# CLOCK_IO.net
KiCad netlist of a schematic drawn in Altium Designer
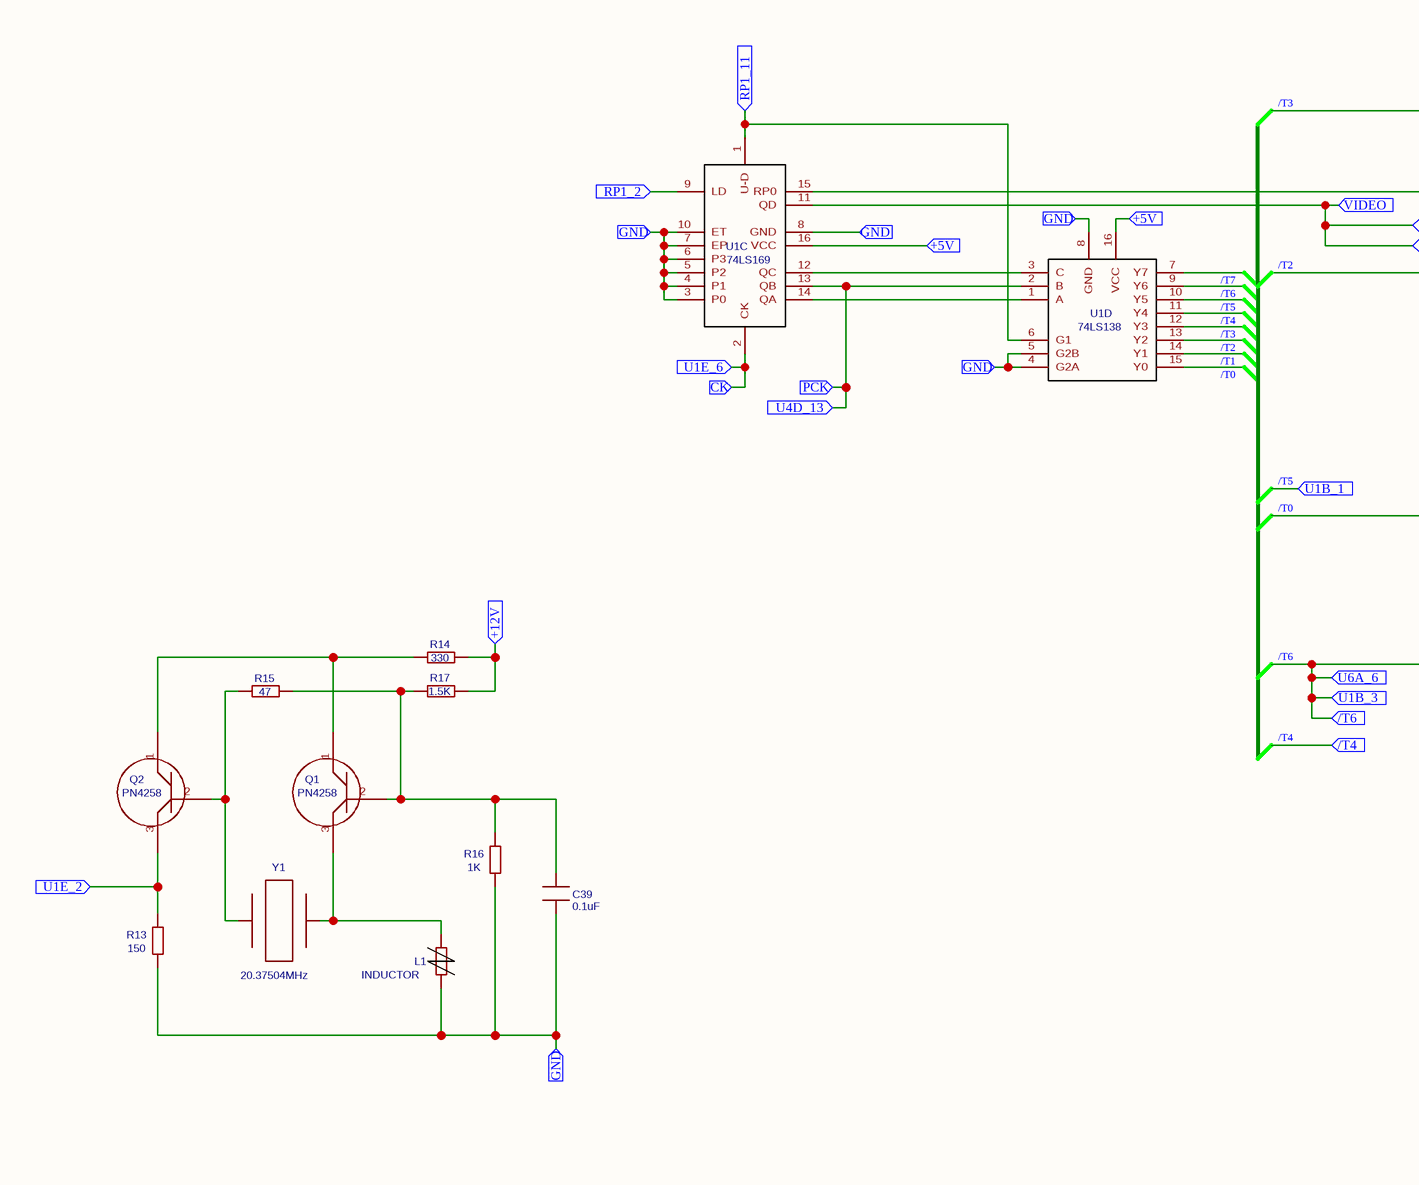
[diagram p0: CLOCK+IO.schdoc, left]
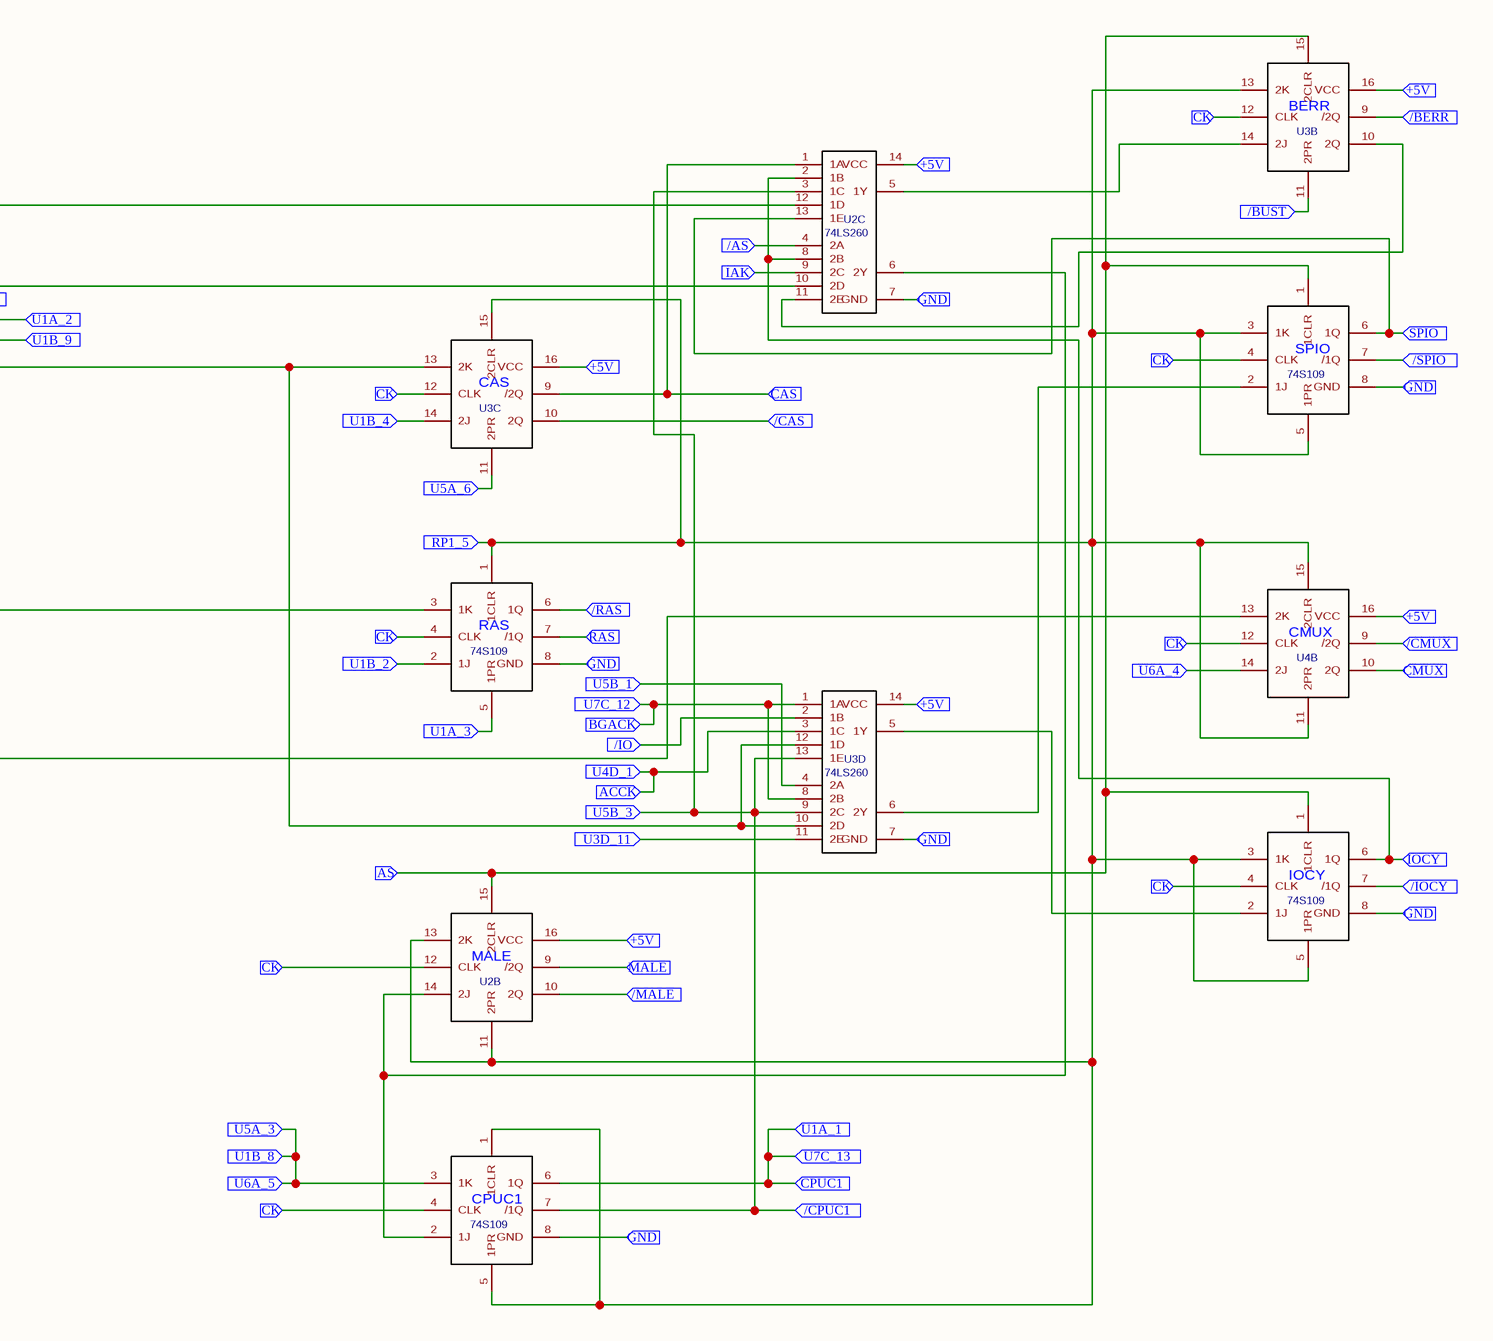
[diagram p1: CLOCK+IO.schdoc, right]

(export (version "E")
  (design (tool "Eeschema 10.0.6"))
  (components
    (comp (ref "C39")
      (value "0.1uF")
      (fields (field (name "CONTRIBUTOR") "William Tooker"))
      (libsource (lib "altium-import") (part "root_3_0.1uF_"))
    )
    (comp (ref "L1")
      (value "INDUCTOR")
      (fields (field (name "CONTRIBUTOR") "William Tooker"))
      (libsource (lib "altium-import") (part "root_3_INDUCTOR_"))
    )
    (comp (ref "Q1")
      (value "PN4258")
      (fields (field (name "CONTRIBUTOR") "William Tooker"))
      (libsource (lib "altium-import") (part "root_0_PN4258_"))
    )
    (comp (ref "Q2")
      (value "PN4258")
      (fields (field (name "CONTRIBUTOR") "William Tooker"))
      (libsource (lib "altium-import") (part "root_0_PN4258_"))
    )
    (comp (ref "R13")
      (value "150")
      (fields (field (name "CONTRIBUTOR") "William Tooker"))
      (libsource (lib "altium-import") (part "root_1_150_"))
    )
    (comp (ref "R14")
      (value "330")
      (fields (field (name "CONTRIBUTOR") "William Tooker"))
      (libsource (lib "altium-import") (part "root_0_330_"))
    )
    (comp (ref "R15")
      (value "47")
      (fields (field (name "CONTRIBUTOR") "William Tooker"))
      (libsource (lib "altium-import") (part "root_0_47_"))
    )
    (comp (ref "R16")
      (value "1K")
      (fields (field (name "CONTRIBUTOR") "William Tooker"))
      (libsource (lib "altium-import") (part "root_1_1K_"))
    )
    (comp (ref "R17")
      (value "1.5K")
      (fields (field (name "CONTRIBUTOR") "William Tooker"))
      (libsource (lib "altium-import") (part "root_0_1.5K_"))
    )
    (comp (ref "U1C")
      (value "74LS169")
      (fields (field (name "CONTRIBUTOR") "William Tooker"))
      (libsource (lib "altium-import") (part "root_0_74LS169_"))
    )
    (comp (ref "U1D")
      (value "74LS138")
      (fields (field (name "CONTRIBUTOR") "William Tooker"))
      (libsource (lib "altium-import") (part "root_0_74LS138_"))
    )
    (comp (ref "U2B")
      (value "74S109")
      (fields (field (name "CONTRIBUTOR") "William Tooker"))
      (libsource (lib "altium-import") (part "root_0_74S109_"))
    )
    (comp (ref "U2C")
      (value "74LS260")
      (fields (field (name "CONTRIBUTOR") "William Tooker"))
      (libsource (lib "altium-import") (part "root_0_74LS260_"))
    )
    (comp (ref "U3B")
      (value "74S109")
      (fields (field (name "CONTRIBUTOR") "William Tooker"))
      (libsource (lib "altium-import") (part "root_0_74S109_"))
    )
    (comp (ref "U3C")
      (value "74S109")
      (fields (field (name "CONTRIBUTOR") "William Tooker"))
      (libsource (lib "altium-import") (part "root_0_74S109_"))
    )
    (comp (ref "U3D")
      (value "74LS260")
      (fields (field (name "CONTRIBUTOR") "William Tooker"))
      (libsource (lib "altium-import") (part "root_0_74LS260_"))
    )
    (comp (ref "U4B")
      (value "74S109")
      (fields (field (name "CONTRIBUTOR") "William Tooker"))
      (libsource (lib "altium-import") (part "root_0_74S109_"))
    )
    (comp (ref "Y1")
      (value "20.37504MHz")
      (fields (field (name "CONTRIBUTOR") "William Tooker"))
      (libsource (lib "altium-import") (part "root_0_20.37504MHz_"))
    )
  )
  (nets
    (net (code "1") (name "/+5V") (class "Default")
      (node (ref "U1C") (pin "16") (pinfunction "VCC_16") (pintype "passive"))
      (node (ref "U1D") (pin "16") (pinfunction "VCC_16") (pintype "passive"))
      (node (ref "U2B") (pin "16") (pinfunction "VCC_16") (pintype "passive"))
      (node (ref "U2C") (pin "14") (pinfunction "VCC_14") (pintype "passive"))
      (node (ref "U3B") (pin "16") (pinfunction "VCC_16") (pintype "passive"))
      (node (ref "U3C") (pin "16") (pinfunction "VCC_16") (pintype "passive"))
      (node (ref "U3D") (pin "14") (pinfunction "VCC_14") (pintype "passive"))
      (node (ref "U4B") (pin "16") (pinfunction "VCC_16") (pintype "passive"))
    )
    (net (code "2") (name "/+12V") (class "Default")
      (node (ref "R14") (pin "2") (pinfunction "2_2") (pintype "passive"))
      (node (ref "R17") (pin "2") (pinfunction "2_2") (pintype "passive"))
    )
    (net (code "3") (name "/ACCK") (class "Default")
      (node (ref "U3D") (pin "3") (pinfunction "1C_3") (pintype "passive"))
    )
    (net (code "4") (name "/AS") (class "Default")
      (node (ref "U2B") (pin "15") (pinfunction "2CLR_15") (pintype "passive"))
      (node (ref "U3B") (pin "1") (pinfunction "1CLR_1") (pintype "passive"))
      (node (ref "U3B") (pin "15") (pinfunction "2CLR_15") (pintype "passive"))
      (node (ref "U4B") (pin "1") (pinfunction "1CLR_1") (pintype "passive"))
    )
    (net (code "5") (name "/BGACK") (class "Default")
      (node (ref "U3D") (pin "1") (pinfunction "1A_1") (pintype "passive"))
      (node (ref "U3D") (pin "8") (pinfunction "2B_8") (pintype "passive"))
    )
    (net (code "6") (name "/CAS") (class "Default")
      (node (ref "U2C") (pin "1") (pinfunction "1A_1") (pintype "passive"))
      (node (ref "U3C") (pin "9") (pinfunction "/2Q_9") (pintype "passive"))
    )
    (net (code "7") (name "/CK") (class "Default")
      (node (ref "U1C") (pin "2") (pinfunction "CK_2") (pintype "passive"))
      (node (ref "U2B") (pin "12") (pinfunction "CLK_12") (pintype "passive"))
      (node (ref "U2B") (pin "4") (pinfunction "CLK_4") (pintype "passive"))
      (node (ref "U3B") (pin "12") (pinfunction "CLK_12") (pintype "passive"))
      (node (ref "U3B") (pin "4") (pinfunction "CLK_4") (pintype "passive"))
      (node (ref "U3C") (pin "12") (pinfunction "CLK_12") (pintype "passive"))
      (node (ref "U3C") (pin "4") (pinfunction "CLK_4") (pintype "passive"))
      (node (ref "U4B") (pin "12") (pinfunction "CLK_12") (pintype "passive"))
      (node (ref "U4B") (pin "4") (pinfunction "CLK_4") (pintype "passive"))
    )
    (net (code "8") (name "/CMUX") (class "Default")
      (node (ref "U4B") (pin "10") (pinfunction "2Q_10") (pintype "passive"))
    )
    (net (code "9") (name "/CPUC1") (class "Default")
      (node (ref "U2B") (pin "6") (pinfunction "1Q_6") (pintype "passive"))
    )
    (net (code "10") (name "/GND") (class "Default")
      (node (ref "C39") (pin "2") (pinfunction "2_2") (pintype "passive"))
      (node (ref "L1") (pin "2") (pinfunction "2_2") (pintype "passive"))
      (node (ref "R13") (pin "1") (pinfunction "1_1") (pintype "passive"))
      (node (ref "R16") (pin "1") (pinfunction "1_1") (pintype "passive"))
      (node (ref "U1C") (pin "10") (pinfunction "ET_10") (pintype "passive"))
      (node (ref "U1C") (pin "3") (pinfunction "P0_3") (pintype "passive"))
      (node (ref "U1C") (pin "4") (pinfunction "P1_4") (pintype "passive"))
      (node (ref "U1C") (pin "5") (pinfunction "P2_5") (pintype "passive"))
      (node (ref "U1C") (pin "6") (pinfunction "P3_6") (pintype "passive"))
      (node (ref "U1C") (pin "7") (pinfunction "EP_7") (pintype "passive"))
      (node (ref "U1C") (pin "8") (pinfunction "GND_8") (pintype "passive"))
      (node (ref "U1D") (pin "4") (pinfunction "G2A_4") (pintype "passive"))
      (node (ref "U1D") (pin "5") (pinfunction "G2B_5") (pintype "passive"))
      (node (ref "U1D") (pin "8") (pinfunction "GND_8") (pintype "passive"))
      (node (ref "U2B") (pin "8") (pinfunction "GND_8") (pintype "passive"))
      (node (ref "U2C") (pin "7") (pinfunction "GND_7") (pintype "passive"))
      (node (ref "U3B") (pin "8") (pinfunction "GND_8") (pintype "passive"))
      (node (ref "U3C") (pin "8") (pinfunction "GND_8") (pintype "passive"))
      (node (ref "U3D") (pin "7") (pinfunction "GND_7") (pintype "passive"))
      (node (ref "U4B") (pin "8") (pinfunction "GND_8") (pintype "passive"))
    )
    (net (code "11") (name "/IAK") (class "Default")
      (node (ref "U2C") (pin "9") (pinfunction "2C_9") (pintype "passive"))
    )
    (net (code "12") (name "/IOCY") (class "Default")
      (node (ref "U2C") (pin "2") (pinfunction "1B_2") (pintype "passive"))
      (node (ref "U2C") (pin "8") (pinfunction "2B_8") (pintype "passive"))
      (node (ref "U4B") (pin "6") (pinfunction "1Q_6") (pintype "passive"))
    )
    (net (code "13") (name "/MALE") (class "Default")
      (node (ref "U2B") (pin "9") (pinfunction "/2Q_9") (pintype "passive"))
    )
    (net (code "14") (name "/PCK") (class "Default")
      (node (ref "U1C") (pin "13") (pinfunction "QB_13") (pintype "passive"))
      (node (ref "U1D") (pin "2") (pinfunction "B_2") (pintype "passive"))
    )
    (net (code "15") (name "/RAS") (class "Default")
      (node (ref "U3C") (pin "7") (pinfunction "/1Q_7") (pintype "passive"))
    )
    (net (code "16") (name "/RP1_2") (class "Default")
      (node (ref "U1C") (pin "9") (pinfunction "LD_9") (pintype "passive"))
    )
    (net (code "17") (name "/RP1_5") (class "Default")
      (node (ref "U2B") (pin "1") (pinfunction "1CLR_1") (pintype "passive"))
      (node (ref "U2B") (pin "11") (pinfunction "2PR_11") (pintype "passive"))
      (node (ref "U2B") (pin "13") (pinfunction "2K_13") (pintype "passive"))
      (node (ref "U2B") (pin "5") (pinfunction "1PR_5") (pintype "passive"))
      (node (ref "U3B") (pin "13") (pinfunction "2K_13") (pintype "passive"))
      (node (ref "U3B") (pin "3") (pinfunction "1K_3") (pintype "passive"))
      (node (ref "U3B") (pin "5") (pinfunction "1PR_5") (pintype "passive"))
      (node (ref "U3C") (pin "1") (pinfunction "1CLR_1") (pintype "passive"))
      (node (ref "U3C") (pin "15") (pinfunction "2CLR_15") (pintype "passive"))
      (node (ref "U4B") (pin "11") (pinfunction "2PR_11") (pintype "passive"))
      (node (ref "U4B") (pin "15") (pinfunction "2CLR_15") (pintype "passive"))
      (node (ref "U4B") (pin "3") (pinfunction "1K_3") (pintype "passive"))
      (node (ref "U4B") (pin "5") (pinfunction "1PR_5") (pintype "passive"))
    )
    (net (code "18") (name "/RP1_11") (class "Default")
      (node (ref "U1C") (pin "1") (pinfunction "U-D_1") (pintype "passive"))
      (node (ref "U1D") (pin "6") (pinfunction "G1_6") (pintype "passive"))
    )
    (net (code "19") (name "/SPIO") (class "Default")
      (node (ref "U2C") (pin "13") (pinfunction "1E_13") (pintype "passive"))
      (node (ref "U3B") (pin "6") (pinfunction "1Q_6") (pintype "passive"))
    )
    (net (code "20") (name "/U1A_2") (class "Default")
      (node (ref "U1C") (pin "11") (pinfunction "QD_11") (pintype "passive"))
    )
    (net (code "21") (name "/U1A_3") (class "Default")
      (node (ref "U3C") (pin "5") (pinfunction "1PR_5") (pintype "passive"))
    )
    (net (code "22") (name "/U1B_2") (class "Default")
      (node (ref "U3C") (pin "2") (pinfunction "1J_2") (pintype "passive"))
    )
    (net (code "23") (name "/U1B_4") (class "Default")
      (node (ref "U3C") (pin "14") (pinfunction "2J_14") (pintype "passive"))
    )
    (net (code "24") (name "/U1B_8") (class "Default")
      (node (ref "U2B") (pin "3") (pinfunction "1K_3") (pintype "passive"))
    )
    (net (code "25") (name "/U1E_2") (class "Default")
      (node (ref "Q2") (pin "3") (pinfunction "3_3") (pintype "passive"))
      (node (ref "R13") (pin "2") (pinfunction "2_2") (pintype "passive"))
    )
    (net (code "26") (name "/U3D_11") (class "Default")
      (node (ref "U3D") (pin "11") (pinfunction "2E_11") (pintype "passive"))
    )
    (net (code "27") (name "/U5A_6") (class "Default")
      (node (ref "U3C") (pin "11") (pinfunction "2PR_11") (pintype "passive"))
    )
    (net (code "28") (name "/U5B_1") (class "Default")
      (node (ref "U3D") (pin "4") (pinfunction "2A_4") (pintype "passive"))
    )
    (net (code "29") (name "/U5B_3") (class "Default")
      (node (ref "U2B") (pin "7") (pinfunction "/1Q_7") (pintype "passive"))
      (node (ref "U2C") (pin "3") (pinfunction "1C_3") (pintype "passive"))
      (node (ref "U3D") (pin "13") (pinfunction "1E_13") (pintype "passive"))
      (node (ref "U3D") (pin "9") (pinfunction "2C_9") (pintype "passive"))
    )
    (net (code "30") (name "/U6A_4") (class "Default")
      (node (ref "U4B") (pin "14") (pinfunction "2J_14") (pintype "passive"))
    )
    (net (code "31") (name "/{slash}AS") (class "Default")
      (node (ref "U2C") (pin "4") (pinfunction "2A_4") (pintype "passive"))
    )
    (net (code "32") (name "/{slash}BERR") (class "Default")
      (node (ref "U3B") (pin "9") (pinfunction "/2Q_9") (pintype "passive"))
    )
    (net (code "33") (name "/{slash}BUST") (class "Default")
      (node (ref "U3B") (pin "11") (pinfunction "2PR_11") (pintype "passive"))
    )
    (net (code "34") (name "/{slash}CAS") (class "Default")
      (node (ref "U3C") (pin "10") (pinfunction "2Q_10") (pintype "passive"))
    )
    (net (code "35") (name "/{slash}CMUX") (class "Default")
      (node (ref "U4B") (pin "9") (pinfunction "/2Q_9") (pintype "passive"))
    )
    (net (code "36") (name "/{slash}IO") (class "Default")
      (node (ref "U3D") (pin "2") (pinfunction "1B_2") (pintype "passive"))
    )
    (net (code "37") (name "/{slash}IOCY") (class "Default")
      (node (ref "U4B") (pin "7") (pinfunction "/1Q_7") (pintype "passive"))
    )
    (net (code "38") (name "/{slash}MALE") (class "Default")
      (node (ref "U2B") (pin "10") (pinfunction "2Q_10") (pintype "passive"))
    )
    (net (code "39") (name "/{slash}RAS") (class "Default")
      (node (ref "U3C") (pin "6") (pinfunction "1Q_6") (pintype "passive"))
    )
    (net (code "40") (name "/{slash}SPIO") (class "Default")
      (node (ref "U3B") (pin "7") (pinfunction "/1Q_7") (pintype "passive"))
    )
    (net (code "41") (name "/{slash}T0") (class "Default")
      (node (ref "U1D") (pin "15") (pinfunction "Y0_15") (pintype "passive"))
      (node (ref "U3C") (pin "3") (pinfunction "1K_3") (pintype "passive"))
    )
    (net (code "42") (name "/{slash}T1") (class "Default")
      (node (ref "U1D") (pin "14") (pinfunction "Y1_14") (pintype "passive"))
    )
    (net (code "43") (name "/{slash}T2") (class "Default")
      (node (ref "U1D") (pin "13") (pinfunction "Y2_13") (pintype "passive"))
      (node (ref "U3C") (pin "13") (pinfunction "2K_13") (pintype "passive"))
      (node (ref "U3D") (pin "10") (pinfunction "2D_10") (pintype "passive"))
      (node (ref "U3D") (pin "12") (pinfunction "1D_12") (pintype "passive"))
    )
    (net (code "44") (name "/{slash}T3") (class "Default")
      (node (ref "U1D") (pin "12") (pinfunction "Y3_12") (pintype "passive"))
      (node (ref "U2C") (pin "12") (pinfunction "1D_12") (pintype "passive"))
    )
    (net (code "45") (name "/{slash}T4") (class "Default")
      (node (ref "U1D") (pin "11") (pinfunction "Y4_11") (pintype "passive"))
    )
    (net (code "46") (name "/{slash}T5") (class "Default")
      (node (ref "U1D") (pin "10") (pinfunction "Y5_10") (pintype "passive"))
    )
    (net (code "47") (name "/{slash}T6") (class "Default")
      (node (ref "U1D") (pin "9") (pinfunction "Y6_9") (pintype "passive"))
      (node (ref "U4B") (pin "13") (pinfunction "2K_13") (pintype "passive"))
    )
    (net (code "48") (name "/{slash}T7") (class "Default")
      (node (ref "U1D") (pin "7") (pinfunction "Y7_7") (pintype "passive"))
    )
    (net (code "49") (name "Net-(C39-Pad1)") (class "Default")
      (node (ref "C39") (pin "1") (pinfunction "1_1") (pintype "passive"))
      (node (ref "Q1") (pin "2") (pinfunction "2_2") (pintype "passive"))
      (node (ref "R15") (pin "2") (pinfunction "2_2") (pintype "passive"))
      (node (ref "R16") (pin "2") (pinfunction "2_2") (pintype "passive"))
      (node (ref "R17") (pin "1") (pinfunction "1_1") (pintype "passive"))
    )
    (net (code "50") (name "Net-(L1-Pad1)") (class "Default")
      (node (ref "L1") (pin "1") (pinfunction "1_1") (pintype "passive"))
      (node (ref "Q1") (pin "3") (pinfunction "3_3") (pintype "passive"))
      (node (ref "Y1") (pin "2") (pinfunction "2_2") (pintype "passive"))
    )
    (net (code "51") (name "Net-(Q1-Pad1)") (class "Default")
      (node (ref "Q1") (pin "1") (pinfunction "1_1") (pintype "passive"))
      (node (ref "Q2") (pin "1") (pinfunction "1_1") (pintype "passive"))
      (node (ref "R14") (pin "1") (pinfunction "1_1") (pintype "passive"))
    )
    (net (code "52") (name "Net-(Q2-Pad2)") (class "Default")
      (node (ref "Q2") (pin "2") (pinfunction "2_2") (pintype "passive"))
      (node (ref "R15") (pin "1") (pinfunction "1_1") (pintype "passive"))
      (node (ref "Y1") (pin "1") (pinfunction "1_1") (pintype "passive"))
    )
    (net (code "53") (name "Net-(U1C-QA)") (class "Default")
      (node (ref "U1C") (pin "14") (pinfunction "QA_14") (pintype "passive"))
      (node (ref "U1D") (pin "1") (pinfunction "A_1") (pintype "passive"))
    )
    (net (code "54") (name "Net-(U1C-QC)") (class "Default")
      (node (ref "U1C") (pin "12") (pinfunction "QC_12") (pintype "passive"))
      (node (ref "U1D") (pin "3") (pinfunction "C_3") (pintype "passive"))
    )
    (net (code "55") (name "Net-(U1C-RP0)") (class "Default")
      (node (ref "U1C") (pin "15") (pinfunction "RP0_15") (pintype "passive"))
      (node (ref "U2C") (pin "10") (pinfunction "2D_10") (pintype "passive"))
    )
    (net (code "56") (name "Net-(U2B-1J)") (class "Default")
      (node (ref "U2B") (pin "14") (pinfunction "2J_14") (pintype "passive"))
      (node (ref "U2B") (pin "2") (pinfunction "1J_2") (pintype "passive"))
      (node (ref "U2C") (pin "6") (pinfunction "2Y_6") (pintype "passive"))
    )
    (net (code "57") (name "Net-(U2C-1Y)") (class "Default")
      (node (ref "U2C") (pin "5") (pinfunction "1Y_5") (pintype "passive"))
      (node (ref "U3B") (pin "14") (pinfunction "2J_14") (pintype "passive"))
    )
    (net (code "58") (name "Net-(U2C-2E)") (class "Default")
      (node (ref "U2C") (pin "11") (pinfunction "2E_11") (pintype "passive"))
      (node (ref "U3B") (pin "10") (pinfunction "2Q_10") (pintype "passive"))
    )
    (net (code "59") (name "Net-(U3B-1J)") (class "Default")
      (node (ref "U3B") (pin "2") (pinfunction "1J_2") (pintype "passive"))
      (node (ref "U3D") (pin "6") (pinfunction "2Y_6") (pintype "passive"))
    )
    (net (code "60") (name "Net-(U3D-1Y)") (class "Default")
      (node (ref "U3D") (pin "5") (pinfunction "1Y_5") (pintype "passive"))
      (node (ref "U4B") (pin "2") (pinfunction "1J_2") (pintype "passive"))
    )
  )
)
